# zumy_carrier_board_rev1.net
KiCad netlist of a schematic drawn in EAGLE
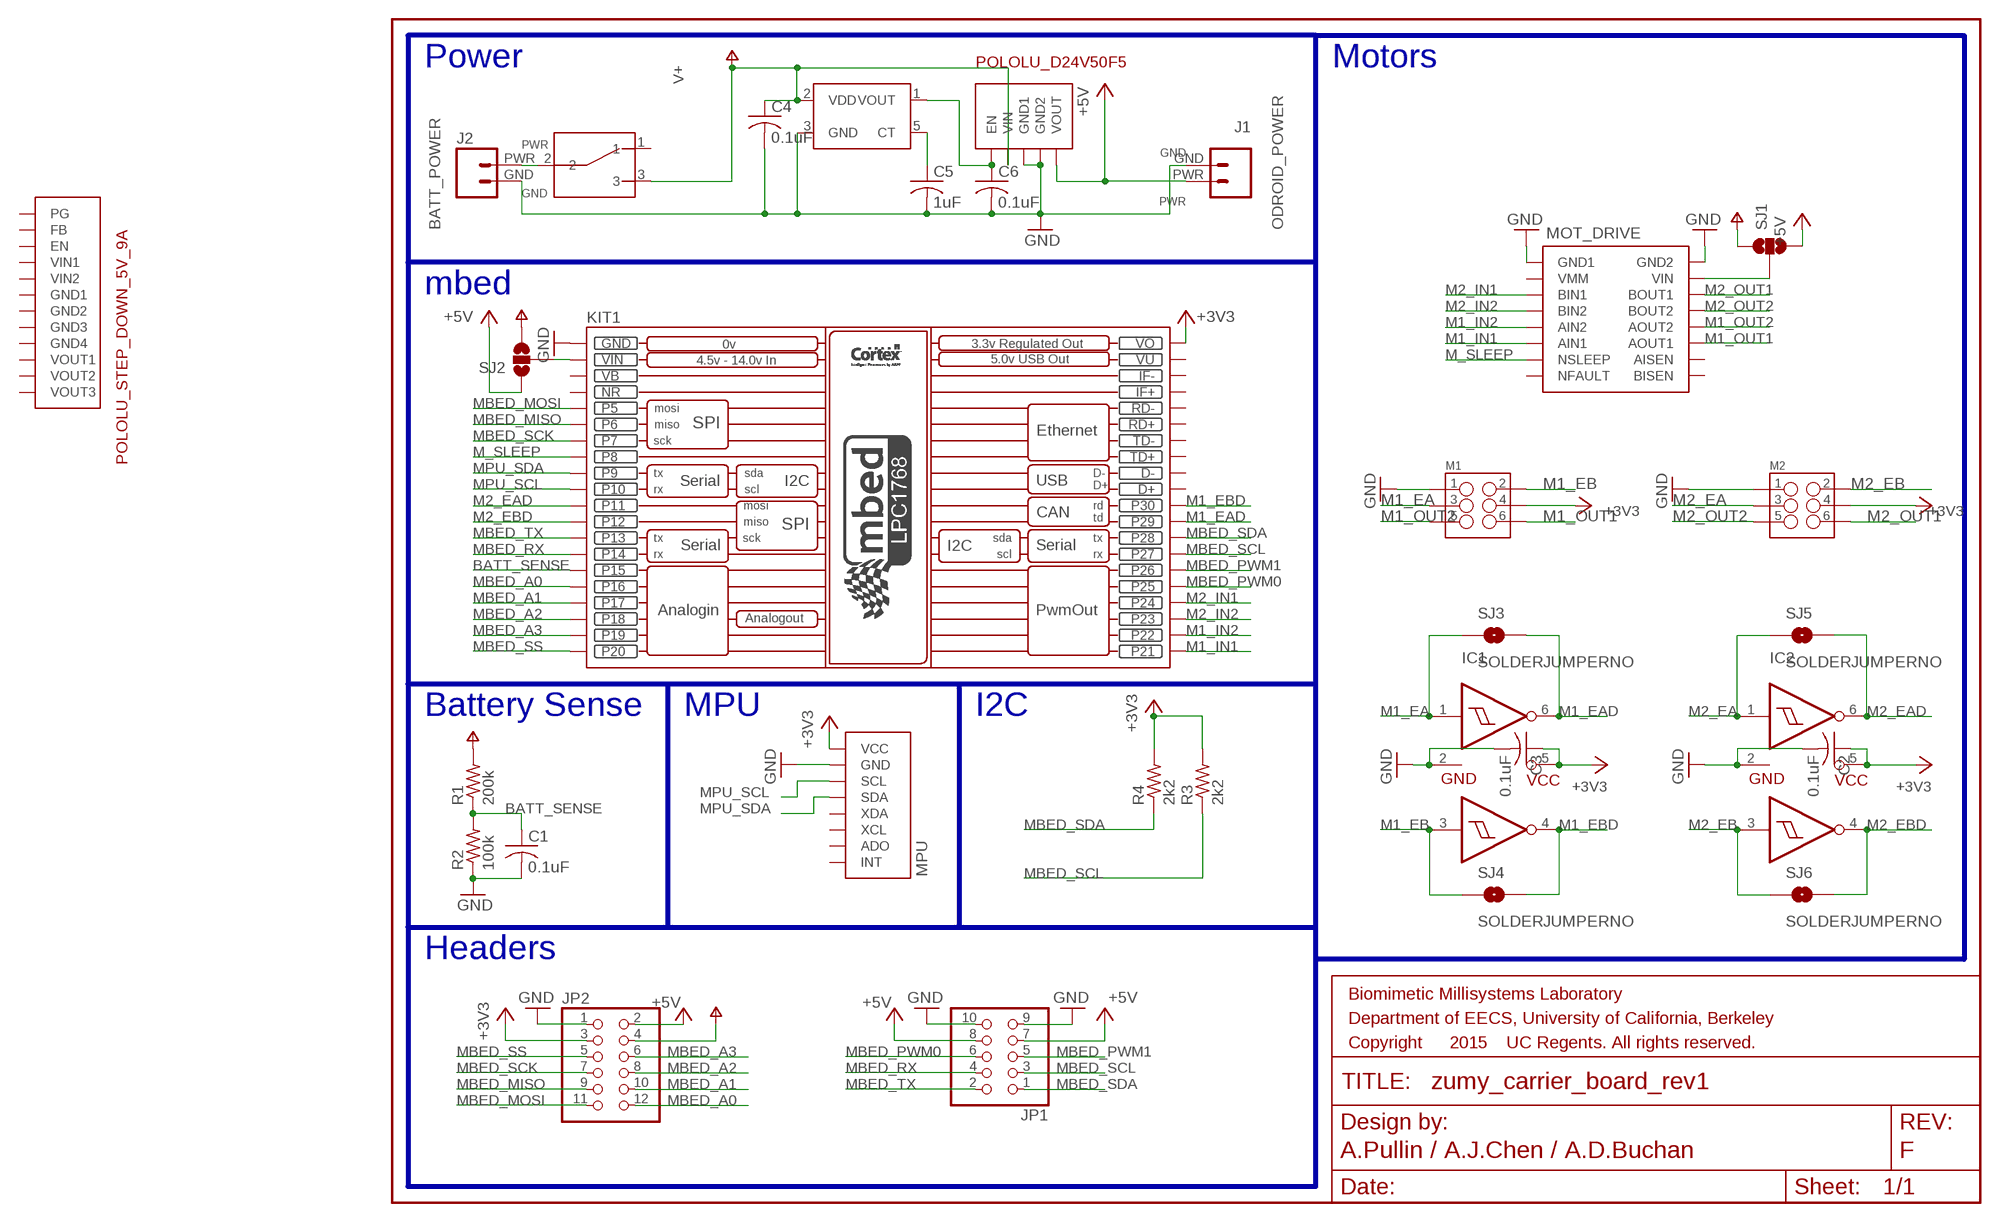
[diagram p0: schematic, sheet 1]

(export (version "E")
  (design (tool "Eeschema 10.0.6"))
  (components
    (comp (ref "C1")
      (value "0.1uF")
      (footprint "eagle-import:C1206")
      (libsource (lib "eagle-import") (part "C-USC1206"))
    )
    (comp (ref "C2")
      (value "0.1uF")
      (footprint "eagle-import:C1206")
      (libsource (lib "eagle-import") (part "C-USC1206"))
    )
    (comp (ref "C3")
      (value "0.1uF")
      (footprint "eagle-import:C1206")
      (libsource (lib "eagle-import") (part "C-USC1206"))
    )
    (comp (ref "C4")
      (value "0.1uF")
      (footprint "eagle-import:C1206")
      (libsource (lib "eagle-import") (part "C-USC1206"))
    )
    (comp (ref "C5")
      (value "1uF")
      (footprint "eagle-import:C1206")
      (libsource (lib "eagle-import") (part "C-USC1206"))
    )
    (comp (ref "C6")
      (value "0.1uF")
      (footprint "eagle-import:C1206")
      (libsource (lib "eagle-import") (part "C-USC1206"))
    )
    (comp (ref "IC1")
      (value "SN74AUP2G17")
      (footprint "eagle-import:SC-70-6")
      (libsource (lib "eagle-import") (part "SN74AUP2G17"))
    )
    (comp (ref "IC2")
      (value "SN74AUP2G17")
      (footprint "eagle-import:SC-70-6")
      (libsource (lib "eagle-import") (part "SN74AUP2G17"))
    )
    (comp (ref "J1")
      (value "ODROID_POWER")
      (footprint "eagle-import:ODOIRD_PWR")
      (libsource (lib "eagle-import") (part "ODROID_POWER"))
    )
    (comp (ref "J2")
      (value "BATT_POWER")
      (footprint "eagle-import:BATT_POWER")
      (libsource (lib "eagle-import") (part "BATT_POWER"))
    )
    (comp (ref "JP1")
      (value "PINHD-2X5")
      (footprint "eagle-import:2X05")
      (libsource (lib "eagle-import") (part "PINHD-2X5"))
    )
    (comp (ref "JP2")
      (value "PINHD-2X6")
      (footprint "eagle-import:2X06")
      (libsource (lib "eagle-import") (part "PINHD-2X6"))
    )
    (comp (ref "KIT1")
      (value "MBED_NXP_LPC1768")
      (footprint "eagle-import:MBED-KIT")
      (libsource (lib "eagle-import") (part "MBED_NXP_LPC1768"))
    )
    (comp (ref "M1")
      (value "M03X2SHROUD")
      (footprint "eagle-import:2X3-SHROUDED")
      (libsource (lib "eagle-import") (part "M03X2SHROUD"))
    )
    (comp (ref "M2")
      (value "M03X2SHROUD")
      (footprint "eagle-import:2X3-SHROUDED")
      (libsource (lib "eagle-import") (part "M03X2SHROUD"))
    )
    (comp (ref "MOT_DRIVE")
      (value "POLOLU_DRV8833_MODULE")
      (footprint "eagle-import:POLOLU_DRV8833_MODULE")
      (libsource (lib "eagle-import") (part "POLOLU_DRV8833_MODULE"))
    )
    (comp (ref "MPU")
      (value "ITG/MPU_MODULE")
      (footprint "eagle-import:ITG_MPU_MODULE")
      (libsource (lib "eagle-import") (part "ITG/MPU_MODULE"))
    )
    (comp (ref "R1")
      (value "200k")
      (footprint "eagle-import:R1206")
      (libsource (lib "eagle-import") (part "R-US_R1206"))
    )
    (comp (ref "R2")
      (value "100k")
      (footprint "eagle-import:R1206")
      (libsource (lib "eagle-import") (part "R-US_R1206"))
    )
    (comp (ref "R3")
      (value "2k2")
      (footprint "eagle-import:R1206")
      (libsource (lib "eagle-import") (part "R-US_R1206"))
    )
    (comp (ref "R4")
      (value "2k2")
      (footprint "eagle-import:R1206")
      (libsource (lib "eagle-import") (part "R-US_R1206"))
    )
    (comp (ref "SJ1")
      (value "SOLDERJUMPER_2WAYT")
      (footprint "eagle-import:SJ_2")
      (libsource (lib "eagle-import") (part "SOLDERJUMPER_2WAYT"))
    )
    (comp (ref "SJ2")
      (value "SOLDERJUMPER_2WAYT")
      (footprint "eagle-import:SJ_2")
      (libsource (lib "eagle-import") (part "SOLDERJUMPER_2WAYT"))
    )
    (comp (ref "SJ3")
      (value "SOLDERJUMPERNO")
      (footprint "eagle-import:SJ_2S-NO")
      (libsource (lib "eagle-import") (part "SOLDERJUMPERNO"))
    )
    (comp (ref "SJ4")
      (value "SOLDERJUMPERNO")
      (footprint "eagle-import:SJ_2S-NO")
      (libsource (lib "eagle-import") (part "SOLDERJUMPERNO"))
    )
    (comp (ref "SJ5")
      (value "SOLDERJUMPERNO")
      (footprint "eagle-import:SJ_2S-NO")
      (libsource (lib "eagle-import") (part "SOLDERJUMPERNO"))
    )
    (comp (ref "SJ6")
      (value "SOLDERJUMPERNO")
      (footprint "eagle-import:SJ_2S-NO")
      (libsource (lib "eagle-import") (part "SOLDERJUMPERNO"))
    )
    (comp (ref "SW1")
      (value "500SSP1S1M6QEA")
      (footprint "eagle-import:500SSP1S1M6QEA_SWITCH")
      (libsource (lib "eagle-import") (part "500SSP1S1M6QEA"))
    )
    (comp (ref "U$2")
      (value "BD5260G")
      (footprint "eagle-import:SOT23-5")
      (libsource (lib "eagle-import") (part "BD5260G"))
    )
    (comp (ref "U$3")
      (value "POLOLU_STEP_DOWN_5V_9A")
      (footprint "eagle-import:POLOLU_STEP_DOWN_5V_9A")
      (libsource (lib "eagle-import") (part "POLOLU_STEP_DOWN_5V_9A"))
    )
    (comp (ref "U$5")
      (value "POLOLU_D24V50F5")
      (footprint "eagle-import:POLOLU_D24V50F5")
      (libsource (lib "eagle-import") (part "POLOLU_D24V50F5"))
    )
  )
  (nets
    (net (code "1") (name "+3V3") (class "Default")
      (node (ref "C2") (pin "1") (pinfunction "1_1") (pintype "passive"))
      (node (ref "C3") (pin "1") (pinfunction "1_1") (pintype "passive"))
      (node (ref "IC1") (pin "5") (pinfunction "VCC_5") (pintype "output"))
      (node (ref "IC2") (pin "5") (pinfunction "VCC_5") (pintype "output"))
      (node (ref "JP2") (pin "3") (pinfunction "3_3") (pintype "passive"))
      (node (ref "KIT1") (pin "VOUT") (pinfunction "VO_VOUT") (pintype "power_in"))
      (node (ref "M1") (pin "4") (pinfunction "4_4") (pintype "bidirectional"))
      (node (ref "M2") (pin "4") (pinfunction "4_4") (pintype "bidirectional"))
      (node (ref "MPU") (pin "VCC") (pinfunction "VCC_VCC") (pintype "bidirectional"))
      (node (ref "R3") (pin "2") (pinfunction "2_2") (pintype "passive"))
      (node (ref "R4") (pin "2") (pinfunction "2_2") (pintype "passive"))
    )
    (net (code "2") (name "+5V") (class "Default")
      (node (ref "J1") (pin "PWR") (pinfunction "PWR_PWR") (pintype "passive"))
      (node (ref "JP1") (pin "7") (pinfunction "7_7") (pintype "passive"))
      (node (ref "JP1") (pin "8") (pinfunction "8_8") (pintype "passive"))
      (node (ref "JP2") (pin "2") (pinfunction "2_2") (pintype "passive"))
      (node (ref "SJ1") (pin "3") (pinfunction "3_3") (pintype "passive"))
      (node (ref "SJ2") (pin "1") (pinfunction "1_1") (pintype "passive"))
      (node (ref "U$5") (pin "VOUT") (pinfunction "VOUT_VOUT") (pintype "bidirectional"))
    )
    (net (code "3") (name "/BATT_SENSE") (class "Default")
      (node (ref "C1") (pin "1") (pinfunction "1_1") (pintype "passive"))
      (node (ref "KIT1") (pin "P$15") (pinfunction "P15_P$15") (pintype "bidirectional"))
      (node (ref "R1") (pin "1") (pinfunction "1_1") (pintype "passive"))
      (node (ref "R2") (pin "2") (pinfunction "2_2") (pintype "passive"))
    )
    (net (code "4") (name "/M1_EA") (class "Default")
      (node (ref "IC1") (pin "1") (pinfunction "1A_1") (pintype "input"))
      (node (ref "M1") (pin "3") (pinfunction "3_3") (pintype "bidirectional"))
      (node (ref "SJ3") (pin "1") (pinfunction "1_1") (pintype "passive"))
    )
    (net (code "5") (name "/M1_EAD") (class "Default")
      (node (ref "IC1") (pin "6") (pinfunction "1Y_6") (pintype "output"))
      (node (ref "KIT1") (pin "P$29") (pinfunction "P29_P$29") (pintype "bidirectional"))
      (node (ref "SJ3") (pin "2") (pinfunction "2_2") (pintype "passive"))
    )
    (net (code "6") (name "/M1_EB") (class "Default")
      (node (ref "IC1") (pin "3") (pinfunction "2A_3") (pintype "input"))
      (node (ref "M1") (pin "2") (pinfunction "2_2") (pintype "bidirectional"))
      (node (ref "SJ4") (pin "1") (pinfunction "1_1") (pintype "passive"))
    )
    (net (code "7") (name "/M1_EBD") (class "Default")
      (node (ref "IC1") (pin "4") (pinfunction "2Y_4") (pintype "output"))
      (node (ref "KIT1") (pin "P$30") (pinfunction "P30_P$30") (pintype "bidirectional"))
      (node (ref "SJ4") (pin "2") (pinfunction "2_2") (pintype "passive"))
    )
    (net (code "8") (name "/M1_IN1") (class "Default")
      (node (ref "KIT1") (pin "P$21") (pinfunction "P21_P$21") (pintype "bidirectional"))
      (node (ref "MOT_DRIVE") (pin "AIN1") (pinfunction "AIN1_AIN1") (pintype "bidirectional"))
    )
    (net (code "9") (name "/M1_IN2") (class "Default")
      (node (ref "KIT1") (pin "P$22") (pinfunction "P22_P$22") (pintype "bidirectional"))
      (node (ref "MOT_DRIVE") (pin "AIN2") (pinfunction "AIN2_AIN2") (pintype "bidirectional"))
    )
    (net (code "10") (name "/M1_OUT1") (class "Default")
      (node (ref "M1") (pin "6") (pinfunction "6_6") (pintype "bidirectional"))
      (node (ref "MOT_DRIVE") (pin "AOUT1") (pinfunction "AOUT1_AOUT1") (pintype "bidirectional"))
    )
    (net (code "11") (name "/M1_OUT2") (class "Default")
      (node (ref "M1") (pin "5") (pinfunction "5_5") (pintype "bidirectional"))
      (node (ref "MOT_DRIVE") (pin "AOUT2") (pinfunction "AOUT2_AOUT2") (pintype "bidirectional"))
    )
    (net (code "12") (name "/M2_EA") (class "Default")
      (node (ref "IC2") (pin "1") (pinfunction "1A_1") (pintype "input"))
      (node (ref "M2") (pin "3") (pinfunction "3_3") (pintype "bidirectional"))
      (node (ref "SJ5") (pin "1") (pinfunction "1_1") (pintype "passive"))
    )
    (net (code "13") (name "/M2_EAD") (class "Default")
      (node (ref "IC2") (pin "6") (pinfunction "1Y_6") (pintype "output"))
      (node (ref "KIT1") (pin "P$11") (pinfunction "P11_P$11") (pintype "bidirectional"))
      (node (ref "SJ5") (pin "2") (pinfunction "2_2") (pintype "passive"))
    )
    (net (code "14") (name "/M2_EB") (class "Default")
      (node (ref "IC2") (pin "3") (pinfunction "2A_3") (pintype "input"))
      (node (ref "M2") (pin "2") (pinfunction "2_2") (pintype "bidirectional"))
      (node (ref "SJ6") (pin "1") (pinfunction "1_1") (pintype "passive"))
    )
    (net (code "15") (name "/M2_EBD") (class "Default")
      (node (ref "IC2") (pin "4") (pinfunction "2Y_4") (pintype "output"))
      (node (ref "KIT1") (pin "P$12") (pinfunction "P12_P$12") (pintype "bidirectional"))
      (node (ref "SJ6") (pin "2") (pinfunction "2_2") (pintype "passive"))
    )
    (net (code "16") (name "/M2_IN1") (class "Default")
      (node (ref "KIT1") (pin "P$24") (pinfunction "P24_P$24") (pintype "bidirectional"))
      (node (ref "MOT_DRIVE") (pin "BIN1") (pinfunction "BIN1_BIN1") (pintype "bidirectional"))
    )
    (net (code "17") (name "/M2_IN2") (class "Default")
      (node (ref "KIT1") (pin "P$23") (pinfunction "P23_P$23") (pintype "bidirectional"))
      (node (ref "MOT_DRIVE") (pin "BIN2") (pinfunction "BIN2_BIN2") (pintype "bidirectional"))
    )
    (net (code "18") (name "/M2_OUT1") (class "Default")
      (node (ref "M2") (pin "6") (pinfunction "6_6") (pintype "bidirectional"))
      (node (ref "MOT_DRIVE") (pin "BOUT1") (pinfunction "BOUT1_BOUT1") (pintype "bidirectional"))
    )
    (net (code "19") (name "/M2_OUT2") (class "Default")
      (node (ref "M2") (pin "5") (pinfunction "5_5") (pintype "bidirectional"))
      (node (ref "MOT_DRIVE") (pin "BOUT2") (pinfunction "BOUT2_BOUT2") (pintype "bidirectional"))
    )
    (net (code "20") (name "/MBED_A0") (class "Default")
      (node (ref "JP2") (pin "12") (pinfunction "12_12") (pintype "passive"))
      (node (ref "KIT1") (pin "P$16") (pinfunction "P16_P$16") (pintype "bidirectional"))
    )
    (net (code "21") (name "/MBED_A1") (class "Default")
      (node (ref "JP2") (pin "10") (pinfunction "10_10") (pintype "passive"))
      (node (ref "KIT1") (pin "P$17") (pinfunction "P17_P$17") (pintype "bidirectional"))
    )
    (net (code "22") (name "/MBED_A2") (class "Default")
      (node (ref "JP2") (pin "8") (pinfunction "8_8") (pintype "passive"))
      (node (ref "KIT1") (pin "P$18") (pinfunction "P18_P$18") (pintype "bidirectional"))
    )
    (net (code "23") (name "/MBED_A3") (class "Default")
      (node (ref "JP2") (pin "6") (pinfunction "6_6") (pintype "passive"))
      (node (ref "KIT1") (pin "P$19") (pinfunction "P19_P$19") (pintype "bidirectional"))
    )
    (net (code "24") (name "/MBED_MISO") (class "Default")
      (node (ref "JP2") (pin "9") (pinfunction "9_9") (pintype "passive"))
      (node (ref "KIT1") (pin "P$6") (pinfunction "P6_P$6") (pintype "bidirectional"))
    )
    (net (code "25") (name "/MBED_MOSI") (class "Default")
      (node (ref "JP2") (pin "11") (pinfunction "11_11") (pintype "passive"))
      (node (ref "KIT1") (pin "P$5") (pinfunction "P5_P$5") (pintype "bidirectional"))
    )
    (net (code "26") (name "/MBED_PWM0") (class "Default")
      (node (ref "JP1") (pin "6") (pinfunction "6_6") (pintype "passive"))
      (node (ref "KIT1") (pin "P$25") (pinfunction "P25_P$25") (pintype "bidirectional"))
    )
    (net (code "27") (name "/MBED_PWM1") (class "Default")
      (node (ref "JP1") (pin "5") (pinfunction "5_5") (pintype "passive"))
      (node (ref "KIT1") (pin "P$26") (pinfunction "P26_P$26") (pintype "bidirectional"))
    )
    (net (code "28") (name "/MBED_RX") (class "Default")
      (node (ref "JP1") (pin "4") (pinfunction "4_4") (pintype "passive"))
      (node (ref "KIT1") (pin "P$14") (pinfunction "P14_P$14") (pintype "bidirectional"))
    )
    (net (code "29") (name "/MBED_SCK") (class "Default")
      (node (ref "JP2") (pin "7") (pinfunction "7_7") (pintype "passive"))
      (node (ref "KIT1") (pin "P$7") (pinfunction "P7_P$7") (pintype "bidirectional"))
    )
    (net (code "30") (name "/MBED_SCL") (class "Default")
      (node (ref "JP1") (pin "3") (pinfunction "3_3") (pintype "passive"))
      (node (ref "KIT1") (pin "P$27") (pinfunction "P27_P$27") (pintype "bidirectional"))
      (node (ref "R3") (pin "1") (pinfunction "1_1") (pintype "passive"))
    )
    (net (code "31") (name "/MBED_SDA") (class "Default")
      (node (ref "JP1") (pin "1") (pinfunction "1_1") (pintype "passive"))
      (node (ref "KIT1") (pin "P$28") (pinfunction "P28_P$28") (pintype "bidirectional"))
      (node (ref "R4") (pin "1") (pinfunction "1_1") (pintype "passive"))
    )
    (net (code "32") (name "/MBED_SS") (class "Default")
      (node (ref "JP2") (pin "5") (pinfunction "5_5") (pintype "passive"))
      (node (ref "KIT1") (pin "P$20") (pinfunction "P20_P$20") (pintype "bidirectional"))
    )
    (net (code "33") (name "/MBED_TX") (class "Default")
      (node (ref "JP1") (pin "2") (pinfunction "2_2") (pintype "passive"))
      (node (ref "KIT1") (pin "P$13") (pinfunction "P13_P$13") (pintype "bidirectional"))
    )
    (net (code "34") (name "/MPU_SCL") (class "Default")
      (node (ref "KIT1") (pin "P$10") (pinfunction "P10_P$10") (pintype "bidirectional"))
      (node (ref "MPU") (pin "SCL") (pinfunction "SCL_SCL") (pintype "bidirectional"))
    )
    (net (code "35") (name "/MPU_SDA") (class "Default")
      (node (ref "KIT1") (pin "P$9") (pinfunction "P9_P$9") (pintype "bidirectional"))
      (node (ref "MPU") (pin "SDA") (pinfunction "SDA_SDA") (pintype "bidirectional"))
    )
    (net (code "36") (name "/M_SLEEP") (class "Default")
      (node (ref "KIT1") (pin "P$8") (pinfunction "P8_P$8") (pintype "bidirectional"))
      (node (ref "MOT_DRIVE") (pin "NSLEEP") (pinfunction "NSLEEP_NSLEEP") (pintype "bidirectional"))
    )
    (net (code "37") (name "/NR") (class "Default")
      (node (ref "KIT1") (pin "NR") (pinfunction "NR_NR") (pintype "power_in"))
    )
    (net (code "38") (name "/VB") (class "Default")
      (node (ref "KIT1") (pin "VB") (pinfunction "VB_VB") (pintype "power_in"))
    )
    (net (code "39") (name "/VU") (class "Default")
      (node (ref "KIT1") (pin "VU") (pinfunction "VU_VU") (pintype "power_in"))
    )
    (net (code "40") (name "GND") (class "Default")
      (node (ref "C1") (pin "2") (pinfunction "2_2") (pintype "passive"))
      (node (ref "C2") (pin "2") (pinfunction "2_2") (pintype "passive"))
      (node (ref "C3") (pin "2") (pinfunction "2_2") (pintype "passive"))
      (node (ref "C4") (pin "2") (pinfunction "2_2") (pintype "passive"))
      (node (ref "C5") (pin "2") (pinfunction "2_2") (pintype "passive"))
      (node (ref "C6") (pin "2") (pinfunction "2_2") (pintype "passive"))
      (node (ref "IC1") (pin "2") (pinfunction "GND_2") (pintype "input"))
      (node (ref "IC2") (pin "2") (pinfunction "GND_2") (pintype "input"))
      (node (ref "J1") (pin "GND") (pinfunction "GND_GND") (pintype "passive"))
      (node (ref "J2") (pin "GND") (pinfunction "GND_GND") (pintype "passive"))
      (node (ref "JP1") (pin "10") (pinfunction "10_10") (pintype "passive"))
      (node (ref "JP1") (pin "9") (pinfunction "9_9") (pintype "passive"))
      (node (ref "JP2") (pin "1") (pinfunction "1_1") (pintype "passive"))
      (node (ref "KIT1") (pin "GND") (pinfunction "GND_GND") (pintype "power_in"))
      (node (ref "M1") (pin "1") (pinfunction "1_1") (pintype "bidirectional"))
      (node (ref "M2") (pin "1") (pinfunction "1_1") (pintype "bidirectional"))
      (node (ref "MOT_DRIVE") (pin "GND1") (pinfunction "GND1_GND1") (pintype "bidirectional"))
      (node (ref "MOT_DRIVE") (pin "GND2") (pinfunction "GND2_GND2") (pintype "bidirectional"))
      (node (ref "MPU") (pin "GND") (pinfunction "GND_GND") (pintype "bidirectional"))
      (node (ref "R2") (pin "1") (pinfunction "1_1") (pintype "passive"))
      (node (ref "U$2") (pin "3") (pinfunction "GND_3") (pintype "bidirectional"))
      (node (ref "U$5") (pin "GND1") (pinfunction "GND1_GND1") (pintype "bidirectional"))
      (node (ref "U$5") (pin "GND2") (pinfunction "GND2_GND2") (pintype "bidirectional"))
    )
    (net (code "41") (name "Net-(J2-PadPWR)") (class "Default")
      (node (ref "J2") (pin "PWR") (pinfunction "PWR_PWR") (pintype "passive"))
      (node (ref "SW1") (pin "2") (pinfunction "2_2") (pintype "bidirectional"))
    )
    (net (code "42") (name "Net-(KIT1-PadVIN)") (class "Default")
      (node (ref "KIT1") (pin "VIN") (pinfunction "VIN_VIN") (pintype "power_in"))
      (node (ref "SJ2") (pin "2") (pinfunction "2_2") (pintype "passive"))
    )
    (net (code "43") (name "Net-(MOT_DRIVE-PadVIN)") (class "Default")
      (node (ref "MOT_DRIVE") (pin "VIN") (pinfunction "VIN_VIN") (pintype "bidirectional"))
      (node (ref "SJ1") (pin "2") (pinfunction "2_2") (pintype "passive"))
    )
    (net (code "44") (name "Net-(U$2-CT)") (class "Default")
      (node (ref "C5") (pin "1") (pinfunction "1_1") (pintype "passive"))
      (node (ref "U$2") (pin "5") (pinfunction "CT_5") (pintype "bidirectional"))
    )
    (net (code "45") (name "Net-(U$2-VOUT)") (class "Default")
      (node (ref "C6") (pin "1") (pinfunction "1_1") (pintype "passive"))
      (node (ref "U$2") (pin "1") (pinfunction "VOUT_1") (pintype "bidirectional"))
      (node (ref "U$5") (pin "EN") (pinfunction "EN_EN") (pintype "bidirectional"))
    )
    (net (code "46") (name "V+") (class "Default")
      (node (ref "C4") (pin "1") (pinfunction "1_1") (pintype "passive"))
      (node (ref "JP2") (pin "4") (pinfunction "4_4") (pintype "passive"))
      (node (ref "R1") (pin "2") (pinfunction "2_2") (pintype "passive"))
      (node (ref "SJ1") (pin "1") (pinfunction "1_1") (pintype "passive"))
      (node (ref "SJ2") (pin "3") (pinfunction "3_3") (pintype "passive"))
      (node (ref "SW1") (pin "3") (pinfunction "3_3") (pintype "bidirectional"))
      (node (ref "U$2") (pin "2") (pinfunction "VDD_2") (pintype "bidirectional"))
      (node (ref "U$5") (pin "VIN") (pinfunction "VIN_VIN") (pintype "bidirectional"))
    )
    (net (code "47") (name "unconnected-(KIT1-PadD+)") (class "Default")
      (node (ref "KIT1") (pin "D+") (pinfunction "D+_D+") (pintype "bidirectional"))
    )
    (net (code "48") (name "unconnected-(KIT1-PadD-)") (class "Default")
      (node (ref "KIT1") (pin "D-") (pinfunction "D-_D-") (pintype "bidirectional"))
    )
    (net (code "49") (name "unconnected-(KIT1-PadIF+)") (class "Default")
      (node (ref "KIT1") (pin "IF+") (pinfunction "IF+_IF+") (pintype "bidirectional"))
    )
    (net (code "50") (name "unconnected-(KIT1-PadIF-)") (class "Default")
      (node (ref "KIT1") (pin "IF-") (pinfunction "IF-_IF-") (pintype "bidirectional"))
    )
    (net (code "51") (name "unconnected-(KIT1-PadRD+)") (class "Default")
      (node (ref "KIT1") (pin "RD+") (pinfunction "RD+_RD+") (pintype "bidirectional"))
    )
    (net (code "52") (name "unconnected-(KIT1-PadRD-)") (class "Default")
      (node (ref "KIT1") (pin "RD-") (pinfunction "RD-_RD-") (pintype "bidirectional"))
    )
    (net (code "53") (name "unconnected-(KIT1-PadTD+)") (class "Default")
      (node (ref "KIT1") (pin "TD+") (pinfunction "TD+_TD+") (pintype "bidirectional"))
    )
    (net (code "54") (name "unconnected-(KIT1-PadTD-)") (class "Default")
      (node (ref "KIT1") (pin "TD-") (pinfunction "TD-_TD-") (pintype "bidirectional"))
    )
    (net (code "55") (name "unconnected-(MOT_DRIVE-PadAISEN)") (class "Default")
      (node (ref "MOT_DRIVE") (pin "AISEN") (pinfunction "AISEN_AISEN") (pintype "bidirectional"))
    )
    (net (code "56") (name "unconnected-(MOT_DRIVE-PadBISEN)") (class "Default")
      (node (ref "MOT_DRIVE") (pin "BISEN") (pinfunction "BISEN_BISEN") (pintype "bidirectional"))
    )
    (net (code "57") (name "unconnected-(MOT_DRIVE-PadNFAULT)") (class "Default")
      (node (ref "MOT_DRIVE") (pin "NFAULT") (pinfunction "NFAULT_NFAULT") (pintype "bidirectional"))
    )
    (net (code "58") (name "unconnected-(MOT_DRIVE-PadVMM)") (class "Default")
      (node (ref "MOT_DRIVE") (pin "VMM") (pinfunction "VMM_VMM") (pintype "bidirectional"))
    )
    (net (code "59") (name "unconnected-(MPU-PadADO)") (class "Default")
      (node (ref "MPU") (pin "ADO") (pinfunction "ADO_ADO") (pintype "bidirectional"))
    )
    (net (code "60") (name "unconnected-(MPU-PadINT)") (class "Default")
      (node (ref "MPU") (pin "INT") (pinfunction "INT_INT") (pintype "bidirectional"))
    )
    (net (code "61") (name "unconnected-(MPU-PadXCL)") (class "Default")
      (node (ref "MPU") (pin "XCL") (pinfunction "XCL_XCL") (pintype "bidirectional"))
    )
    (net (code "62") (name "unconnected-(MPU-PadXDA)") (class "Default")
      (node (ref "MPU") (pin "XDA") (pinfunction "XDA_XDA") (pintype "bidirectional"))
    )
    (net (code "63") (name "unconnected-(SW1-Pad1)") (class "Default")
      (node (ref "SW1") (pin "1") (pinfunction "1_1") (pintype "bidirectional"))
    )
    (net (code "64") (name "unconnected-(U$3-PadEN)") (class "Default")
      (node (ref "U$3") (pin "EN") (pinfunction "EN_EN") (pintype "bidirectional"))
    )
    (net (code "65") (name "unconnected-(U$3-PadFB)") (class "Default")
      (node (ref "U$3") (pin "FB") (pinfunction "FB_FB") (pintype "bidirectional"))
    )
    (net (code "66") (name "unconnected-(U$3-PadGND1)") (class "Default")
      (node (ref "U$3") (pin "GND1") (pinfunction "GND1_GND1") (pintype "bidirectional"))
    )
    (net (code "67") (name "unconnected-(U$3-PadGND2)") (class "Default")
      (node (ref "U$3") (pin "GND2") (pinfunction "GND2_GND2") (pintype "bidirectional"))
    )
    (net (code "68") (name "unconnected-(U$3-PadGND3)") (class "Default")
      (node (ref "U$3") (pin "GND3") (pinfunction "GND3_GND3") (pintype "bidirectional"))
    )
    (net (code "69") (name "unconnected-(U$3-PadGND4)") (class "Default")
      (node (ref "U$3") (pin "GND4") (pinfunction "GND4_GND4") (pintype "bidirectional"))
    )
    (net (code "70") (name "unconnected-(U$3-PadPG)") (class "Default")
      (node (ref "U$3") (pin "PG") (pinfunction "PG_PG") (pintype "bidirectional"))
    )
    (net (code "71") (name "unconnected-(U$3-PadVIN1)") (class "Default")
      (node (ref "U$3") (pin "VIN1") (pinfunction "VIN1_VIN1") (pintype "bidirectional"))
    )
    (net (code "72") (name "unconnected-(U$3-PadVIN2)") (class "Default")
      (node (ref "U$3") (pin "VIN2") (pinfunction "VIN2_VIN2") (pintype "bidirectional"))
    )
    (net (code "73") (name "unconnected-(U$3-PadVOUT1)") (class "Default")
      (node (ref "U$3") (pin "VOUT1") (pinfunction "VOUT1_VOUT1") (pintype "bidirectional"))
    )
    (net (code "74") (name "unconnected-(U$3-PadVOUT2)") (class "Default")
      (node (ref "U$3") (pin "VOUT2") (pinfunction "VOUT2_VOUT2") (pintype "bidirectional"))
    )
    (net (code "75") (name "unconnected-(U$3-PadVOUT3)") (class "Default")
      (node (ref "U$3") (pin "VOUT3") (pinfunction "VOUT3_VOUT3") (pintype "bidirectional"))
    )
  )
)
